# CONNECTIVITY.net
KiCad netlist of a schematic drawn in Altium Designer
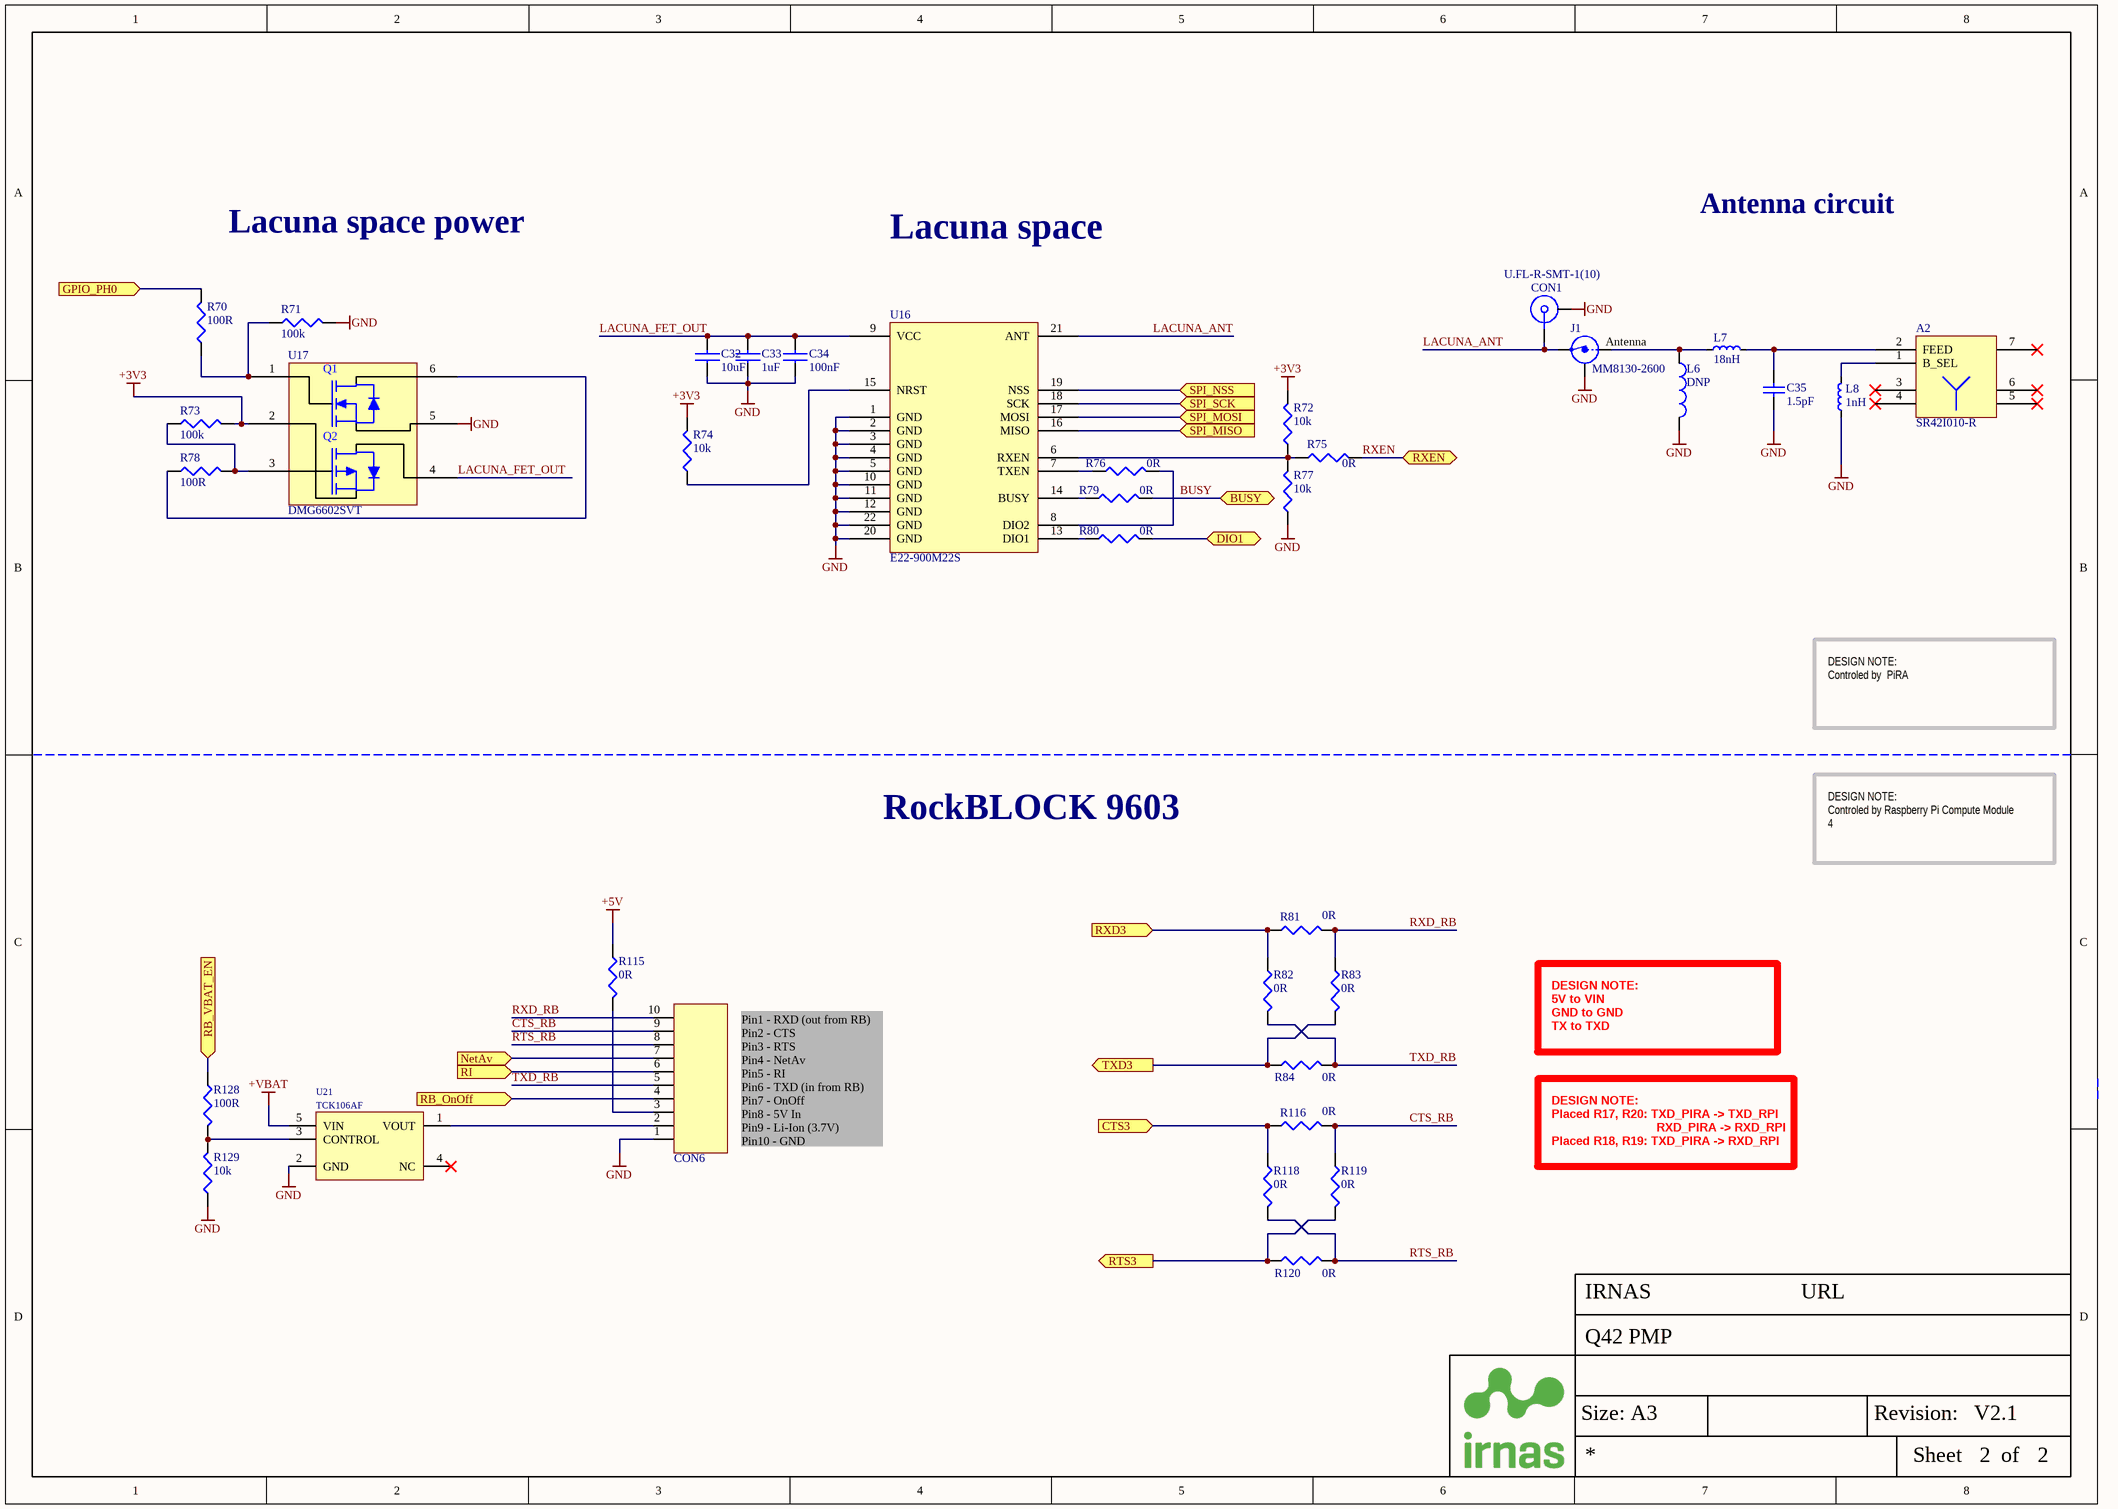
[diagram p0: CONNECTIVITY.SchDoc]

(export (version "E")
  (design (tool "Eeschema 10.0.6"))
  (components
    (comp (ref "A2")
      (value "SR42I010-R")
      (footprint "LORA_PCB_ANTENNA")
      (description "Antenna SMD -4dBi Gain 870MHz/928MHz Automotive 7-Pin SMD T/R")
      (fields (field (name "MANUFACTURER") "Antenova"))
      (libsource (lib "Passive") (part "ANT - SR42I010-L"))
    )
    (comp (ref "C32")
      (value "10uF")
      (footprint "CAP0603")
      (description "Cap Ceramic 10uF 10V X5R 10% SMD 0603 85C Paper T/R")
      (fields
        (field (name "MANUFACTURER") "Samsung")
        (field (name "MANUFACTURER PART NUMBER") "CL10A106KP8NNNC")
      )
      (libsource (lib "Passive") (part "C - 10uF/10V"))
    )
    (comp (ref "C33")
      (value "1uF")
      (footprint "CAP0603")
      (description "MURATA - GRM188R61H105KAALD - CAP, MLCC, X5R, 1UF, 50V, 0603")
      (fields
        (field (name "MANUFACTURER") "MURATA")
        (field (name "MANUFACTURER PART NUMBER") "GRM188R61H105KAALD")
      )
      (libsource (lib "Passive") (part "C - 1uF"))
    )
    (comp (ref "C34")
      (value "100nF")
      (footprint "CAP0603")
      (description "MURATA - GRM188R71C104KA01J - CAP, MLCC, X7R, 0.1UF, 16V, 0603")
      (fields
        (field (name "MANUFACTURER") "MURATA")
        (field (name "MANUFACTURER PART NUMBER") "GRM188R71C104KA01J")
      )
      (libsource (lib "Passive") (part "C - 100nF"))
    )
    (comp (ref "C35")
      (value "1.5pF")
      (footprint "CAP0402")
      (description "CAP CER 1.5PF 50V C0G/NP0 0402")
      (fields (field (name "Comment") "1.5pF/50V/0402") (field (name "PUBLISHER") "Altium Limited"))
      (libsource (lib "Passive") (part "C - 1.5pF/50V/0402"))
    )
    (comp (ref "CON1")
      (value "U.FL-R-SMT-1(10)")
      (footprint "ufl connector smd")
      (description "RF / Coaxial Connector, U.FL Coaxial, Straight Jack, Surface Mount Vertical, 50 ohm, Brass")
      (fields (field (name "MANUFACTURER") "Hirose"))
      (libsource (lib "Connectors") (part "U.FL-R-SMT-1(10)"))
    )
    (comp (ref "CON6")
      (value "53261-1071")
      (footprint "PICOBLADE 10PIN")
      (description "Wire-To-Board Connector, Right Angle, 1.25 mm, 10 Contacts, Header, PicoBlade 53261 Series")
      (libsource (lib "Connectors") (part "PicoBlade 10pin"))
    )
    (comp (ref "J1")
      (value "MM8130-2600")
      (footprint "COAXIAL-SWF")
      (description "Coaxial Connector with Switch")
      (fields
        (field (name "MANUFACTURER") "Murata")
        (field (name "2ND SOURCE PART NUMBER") "81-MM8130-2600RA2")
        (field (name "PUBLISHER") "Nordic Semiconductor")
      )
      (libsource (lib "Connectors") (part "Coaxial-Internal-SW"))
    )
    (comp (ref "L6")
      (value "DNP")
      (footprint "IND0402")
      (description "Inductor RF Chip Multi-Layer 4.3nH 0.3nH 100MHz 8Q-Factor Air 300mA 210mOhm DCR 0402 Paper T/R")
      (fields
        (field (name "MANUFACTURER") "Murata")
        (field (name "MANUFACTURER PART NUMBER") "LQG15HN4N3S02D")
      )
      (libsource (lib "Passive") (part "L - 4.3nH/0402"))
    )
    (comp (ref "L7")
      (value "18nH")
      (footprint "IND0402")
      (description "18 nH, 0.8 ohm, 2.3 GHz, 260 mA, 0402")
      (fields
        (field (name "MANUFACTURER") "MURATA")
        (field (name "MANUFACTURER PART NUMBER") "LQG15WH18NJ02D")
        (field (name "PUBLISHER") "Altium Limited")
      )
      (libsource (lib "Passive") (part "L - 18nH/230mA/0402"))
    )
    (comp (ref "L8")
      (value "1nH")
      (footprint "IND0402")
      (description "Multilayer Inductor, 1 nH, 0.07 ohm, 10 GHz, 1 A, 0402 [1005 Metric], LQG15HS_02 Series")
      (libsource (lib "Passive") (part "L - 1nH/0402"))
    )
    (comp (ref "R70")
      (value "100R")
      (footprint "RES0603")
      (description "MULTICOMP - MC0063W06031100R - RES, THICK FILM, 100R, 1%, 0.063W, 0603")
      (fields
        (field (name "MANUFACTURER") "MULTICOMP")
        (field (name "MANUFACTURER PART NUMBER") "MC0063W06031100R")
      )
      (libsource (lib "Passive") (part "R - 100R"))
    )
    (comp (ref "R71")
      (value "100k")
      (footprint "RES0603")
      (description "MULTICOMP - MCMR06X104 JTL - RES, CERAMIC, 100K, 5%, 0.1W, 0603")
      (fields
        (field (name "MANUFACTURER") "MULTICOMP")
        (field (name "MANUFACTURER PART NUMBER") "MCMR06X104 JTL")
      )
      (libsource (lib "Passive") (part "R - 100k"))
    )
    (comp (ref "R72")
      (value "10k")
      (footprint "RES0603")
      (description "MULTICOMP - MCMR06X103 JTL - RES, CERAMIC, 10K, 5%, 0.1W, 0603")
      (fields
        (field (name "MANUFACTURER") "MULTICOMP")
        (field (name "MANUFACTURER PART NUMBER") "MCMR06X103 JTL")
      )
      (libsource (lib "Passive") (part "R - 10k"))
    )
    (comp (ref "R73")
      (value "100k")
      (footprint "RES0603")
      (description "MULTICOMP - MCMR06X104 JTL - RES, CERAMIC, 100K, 5%, 0.1W, 0603")
      (fields
        (field (name "MANUFACTURER") "MULTICOMP")
        (field (name "MANUFACTURER PART NUMBER") "MCMR06X104 JTL")
      )
      (libsource (lib "Passive") (part "R - 100k"))
    )
    (comp (ref "R74")
      (value "10k")
      (footprint "RES0603")
      (description "MULTICOMP - MCMR06X103 JTL - RES, CERAMIC, 10K, 5%, 0.1W, 0603")
      (fields
        (field (name "MANUFACTURER") "MULTICOMP")
        (field (name "MANUFACTURER PART NUMBER") "MCMR06X103 JTL")
      )
      (libsource (lib "Passive") (part "R - 10k"))
    )
    (comp (ref "R75")
      (value "0R")
      (footprint "RES0603")
      (description "BOURNS - CR0603-J/-000ELF - RES, THICK FILM, 0R, 5%, 0.1W, 0603")
      (fields
        (field (name "MANUFACTURER") "BOURNS")
        (field (name "MANUFACTURER PART NUMBER") "CR0603-J/-000ELF")
      )
      (libsource (lib "Passive") (part "R - 0R"))
    )
    (comp (ref "R76")
      (value "0R")
      (footprint "RES0603")
      (description "BOURNS - CR0603-J/-000ELF - RES, THICK FILM, 0R, 5%, 0.1W, 0603")
      (fields
        (field (name "MANUFACTURER") "BOURNS")
        (field (name "MANUFACTURER PART NUMBER") "CR0603-J/-000ELF")
      )
      (libsource (lib "Passive") (part "R - 0R"))
    )
    (comp (ref "R77")
      (value "10k")
      (footprint "RES0603")
      (description "MULTICOMP - MCMR06X103 JTL - RES, CERAMIC, 10K, 5%, 0.1W, 0603")
      (fields
        (field (name "MANUFACTURER") "MULTICOMP")
        (field (name "MANUFACTURER PART NUMBER") "MCMR06X103 JTL")
      )
      (libsource (lib "Passive") (part "R - 10k"))
    )
    (comp (ref "R78")
      (value "100R")
      (footprint "RES0603")
      (description "MULTICOMP - MC0063W06031100R - RES, THICK FILM, 100R, 1%, 0.063W, 0603")
      (fields
        (field (name "MANUFACTURER") "MULTICOMP")
        (field (name "MANUFACTURER PART NUMBER") "MC0063W06031100R")
      )
      (libsource (lib "Passive") (part "R - 100R"))
    )
    (comp (ref "R79")
      (value "0R")
      (footprint "RES0603")
      (description "BOURNS - CR0603-J/-000ELF - RES, THICK FILM, 0R, 5%, 0.1W, 0603")
      (fields
        (field (name "MANUFACTURER") "BOURNS")
        (field (name "MANUFACTURER PART NUMBER") "CR0603-J/-000ELF")
      )
      (libsource (lib "Passive") (part "R - 0R"))
    )
    (comp (ref "R80")
      (value "0R")
      (footprint "RES0603")
      (description "BOURNS - CR0603-J/-000ELF - RES, THICK FILM, 0R, 5%, 0.1W, 0603")
      (fields
        (field (name "MANUFACTURER") "BOURNS")
        (field (name "MANUFACTURER PART NUMBER") "CR0603-J/-000ELF")
      )
      (libsource (lib "Passive") (part "R - 0R"))
    )
    (comp (ref "R81")
      (value "0R")
      (footprint "RES0603")
      (description "BOURNS - CR0603-J/-000ELF - RES, THICK FILM, 0R, 5%, 0.1W, 0603")
      (fields
        (field (name "MANUFACTURER") "BOURNS")
        (field (name "MANUFACTURER PART NUMBER") "CR0603-J/-000ELF")
      )
      (libsource (lib "Passive") (part "R - 0R"))
    )
    (comp (ref "R82")
      (value "0R")
      (footprint "RES0603")
      (description "BOURNS - CR0603-J/-000ELF - RES, THICK FILM, 0R, 5%, 0.1W, 0603")
      (fields
        (field (name "MANUFACTURER") "BOURNS")
        (field (name "MANUFACTURER PART NUMBER") "CR0603-J/-000ELF")
      )
      (libsource (lib "Passive") (part "R - 0R"))
    )
    (comp (ref "R83")
      (value "0R")
      (footprint "RES0603")
      (description "BOURNS - CR0603-J/-000ELF - RES, THICK FILM, 0R, 5%, 0.1W, 0603")
      (fields
        (field (name "MANUFACTURER") "BOURNS")
        (field (name "MANUFACTURER PART NUMBER") "CR0603-J/-000ELF")
      )
      (libsource (lib "Passive") (part "R - 0R"))
    )
    (comp (ref "R84")
      (value "0R")
      (footprint "RES0603")
      (description "BOURNS - CR0603-J/-000ELF - RES, THICK FILM, 0R, 5%, 0.1W, 0603")
      (fields
        (field (name "MANUFACTURER") "BOURNS")
        (field (name "MANUFACTURER PART NUMBER") "CR0603-J/-000ELF")
      )
      (libsource (lib "Passive") (part "R - 0R"))
    )
    (comp (ref "R115")
      (value "0R")
      (footprint "RES0603")
      (description "BOURNS - CR0603-J/-000ELF - RES, THICK FILM, 0R, 5%, 0.1W, 0603")
      (fields
        (field (name "MANUFACTURER") "BOURNS")
        (field (name "MANUFACTURER PART NUMBER") "CR0603-J/-000ELF")
      )
      (libsource (lib "Passive") (part "R - 0R"))
    )
    (comp (ref "R116")
      (value "0R")
      (footprint "RES0603")
      (description "BOURNS - CR0603-J/-000ELF - RES, THICK FILM, 0R, 5%, 0.1W, 0603")
      (fields
        (field (name "MANUFACTURER") "BOURNS")
        (field (name "MANUFACTURER PART NUMBER") "CR0603-J/-000ELF")
      )
      (libsource (lib "Passive") (part "R - 0R"))
    )
    (comp (ref "R118")
      (value "0R")
      (footprint "RES0603")
      (description "BOURNS - CR0603-J/-000ELF - RES, THICK FILM, 0R, 5%, 0.1W, 0603")
      (fields
        (field (name "MANUFACTURER") "BOURNS")
        (field (name "MANUFACTURER PART NUMBER") "CR0603-J/-000ELF")
      )
      (libsource (lib "Passive") (part "R - 0R"))
    )
    (comp (ref "R119")
      (value "0R")
      (footprint "RES0603")
      (description "BOURNS - CR0603-J/-000ELF - RES, THICK FILM, 0R, 5%, 0.1W, 0603")
      (fields
        (field (name "MANUFACTURER") "BOURNS")
        (field (name "MANUFACTURER PART NUMBER") "CR0603-J/-000ELF")
      )
      (libsource (lib "Passive") (part "R - 0R"))
    )
    (comp (ref "R120")
      (value "0R")
      (footprint "RES0603")
      (description "BOURNS - CR0603-J/-000ELF - RES, THICK FILM, 0R, 5%, 0.1W, 0603")
      (fields
        (field (name "MANUFACTURER") "BOURNS")
        (field (name "MANUFACTURER PART NUMBER") "CR0603-J/-000ELF")
      )
      (libsource (lib "Passive") (part "R - 0R"))
    )
    (comp (ref "R128")
      (value "100R")
      (footprint "RES0603")
      (description "MULTICOMP - MC0063W06031100R - RES, THICK FILM, 100R, 1%, 0.063W, 0603")
      (fields
        (field (name "MANUFACTURER") "MULTICOMP")
        (field (name "MANUFACTURER PART NUMBER") "MC0063W06031100R")
      )
      (libsource (lib "Passive") (part "R - 100R"))
    )
    (comp (ref "R129")
      (value "10k")
      (footprint "RES0603")
      (description "MULTICOMP - MCMR06X103 JTL - RES, CERAMIC, 10K, 5%, 0.1W, 0603")
      (fields
        (field (name "MANUFACTURER") "MULTICOMP")
        (field (name "MANUFACTURER PART NUMBER") "MCMR06X103 JTL")
      )
      (libsource (lib "Passive") (part "R - 10k"))
    )
    (comp (ref "U16")
      (value "E22-900M22S")
      (footprint "E22-900M22S")
      (libsource (lib "Active") (part "RF - E22-900M22S"))
    )
    (comp (ref "U17")
      (value "DMG6602SVT")
      (footprint "TSOT26")
      (description "Dual MOSFET, N and P Channel, 3.4 A, 30 V, 0.038 ohm, 10 V, 1 V")
      (libsource (lib "Active") (part "T_M - DMG6602SVT"))
    )
    (comp (ref "U21")
      (value "TCK106AF")
      (footprint "SOT-25")
      (description "1.0 A Load Switch IC")
      (libsource (lib "Active") (part "SW - TCK106AF"))
    )
  )
  (nets
    (net (code "1") (name "+3V3") (class "Default")
      (node (ref "R72") (pin "2") (pinfunction "2_2") (pintype "passive"))
      (node (ref "R73") (pin "2") (pinfunction "2_2") (pintype "passive"))
      (node (ref "R74") (pin "2") (pinfunction "2_2") (pintype "passive"))
      (node (ref "U17") (pin "2") (pinfunction "S2_2") (pintype "open_collector"))
    )
    (net (code "2") (name "+5V") (class "Default")
      (node (ref "R115") (pin "1") (pinfunction "1_1") (pintype "passive"))
    )
    (net (code "3") (name "+VBAT") (class "Default")
      (node (ref "U21") (pin "5") (pinfunction "VIN_5") (pintype "passive"))
    )
    (net (code "4") (name "/BUSY") (class "Default")
      (node (ref "R79") (pin "2") (pinfunction "2_2") (pintype "passive"))
    )
    (net (code "5") (name "/CTS3") (class "Default")
      (node (ref "R116") (pin "1") (pinfunction "1_1") (pintype "passive"))
      (node (ref "R118") (pin "1") (pinfunction "1_1") (pintype "passive"))
    )
    (net (code "6") (name "/CTS_RB") (class "Default")
      (node (ref "CON6") (pin "9") (pinfunction "9_9") (pintype "passive"))
      (node (ref "R116") (pin "2") (pinfunction "2_2") (pintype "passive"))
      (node (ref "R119") (pin "1") (pinfunction "1_1") (pintype "passive"))
    )
    (net (code "7") (name "/DIO1") (class "Default")
      (node (ref "R80") (pin "2") (pinfunction "2_2") (pintype "passive"))
    )
    (net (code "8") (name "/GPIO_PH0") (class "Default")
      (node (ref "R70") (pin "2") (pinfunction "2_2") (pintype "passive"))
    )
    (net (code "9") (name "/LACUNA_ANT") (class "Default")
      (node (ref "CON1") (pin "1") (pinfunction "1_1") (pintype "open_collector"))
      (node (ref "J1") (pin "3") (pinfunction "OUT_3") (pintype "passive"))
      (node (ref "U16") (pin "21") (pinfunction "ANT_21") (pintype "passive"))
    )
    (net (code "10") (name "/LACUNA_FET_OUT") (class "Default")
      (node (ref "C32") (pin "2") (pinfunction "2_2") (pintype "passive"))
      (node (ref "C33") (pin "2") (pinfunction "2_2") (pintype "passive"))
      (node (ref "C34") (pin "2") (pinfunction "2_2") (pintype "passive"))
      (node (ref "U16") (pin "9") (pinfunction "VCC_9") (pintype "passive"))
      (node (ref "U17") (pin "4") (pinfunction "D2_4") (pintype "open_collector"))
    )
    (net (code "11") (name "/NetAv") (class "Default")
      (node (ref "CON6") (pin "7") (pinfunction "7_7") (pintype "passive"))
    )
    (net (code "12") (name "/RB_OnOff") (class "Default")
      (node (ref "CON6") (pin "4") (pinfunction "4_4") (pintype "passive"))
    )
    (net (code "13") (name "/RB_VBAT_EN") (class "Default")
      (node (ref "R128") (pin "1") (pinfunction "1_1") (pintype "passive"))
    )
    (net (code "14") (name "/RI") (class "Default")
      (node (ref "CON6") (pin "6") (pinfunction "6_6") (pintype "passive"))
    )
    (net (code "15") (name "/RTS3") (class "Default")
      (node (ref "R119") (pin "2") (pinfunction "2_2") (pintype "passive"))
      (node (ref "R120") (pin "1") (pinfunction "1_1") (pintype "passive"))
    )
    (net (code "16") (name "/RTS_RB") (class "Default")
      (node (ref "CON6") (pin "8") (pinfunction "8_8") (pintype "passive"))
      (node (ref "R118") (pin "2") (pinfunction "2_2") (pintype "passive"))
      (node (ref "R120") (pin "2") (pinfunction "2_2") (pintype "passive"))
    )
    (net (code "17") (name "/RXD3") (class "Default")
      (node (ref "R81") (pin "1") (pinfunction "1_1") (pintype "passive"))
      (node (ref "R82") (pin "1") (pinfunction "1_1") (pintype "passive"))
    )
    (net (code "18") (name "/RXD_RB") (class "Default")
      (node (ref "CON6") (pin "10") (pinfunction "10_10") (pintype "passive"))
      (node (ref "R81") (pin "2") (pinfunction "2_2") (pintype "passive"))
      (node (ref "R83") (pin "1") (pinfunction "1_1") (pintype "passive"))
    )
    (net (code "19") (name "/RXEN") (class "Default")
      (node (ref "R75") (pin "2") (pinfunction "2_2") (pintype "passive"))
    )
    (net (code "20") (name "/SPI_MISO") (class "Default")
      (node (ref "U16") (pin "16") (pinfunction "MISO_16") (pintype "passive"))
    )
    (net (code "21") (name "/SPI_MOSI") (class "Default")
      (node (ref "U16") (pin "17") (pinfunction "MOSI_17") (pintype "passive"))
    )
    (net (code "22") (name "/SPI_NSS") (class "Default")
      (node (ref "U16") (pin "19") (pinfunction "NSS_19") (pintype "passive"))
    )
    (net (code "23") (name "/SPI_SCK") (class "Default")
      (node (ref "U16") (pin "18") (pinfunction "SCK_18") (pintype "passive"))
    )
    (net (code "24") (name "/TXD3") (class "Default")
      (node (ref "R83") (pin "2") (pinfunction "2_2") (pintype "passive"))
      (node (ref "R84") (pin "1") (pinfunction "1_1") (pintype "passive"))
    )
    (net (code "25") (name "/TXD_RB") (class "Default")
      (node (ref "CON6") (pin "5") (pinfunction "5_5") (pintype "passive"))
      (node (ref "R82") (pin "2") (pinfunction "2_2") (pintype "passive"))
      (node (ref "R84") (pin "2") (pinfunction "2_2") (pintype "passive"))
    )
    (net (code "26") (name "GND") (class "Default")
      (node (ref "C32") (pin "1") (pinfunction "1_1") (pintype "passive"))
      (node (ref "C33") (pin "1") (pinfunction "1_1") (pintype "passive"))
      (node (ref "C34") (pin "1") (pinfunction "1_1") (pintype "passive"))
      (node (ref "C35") (pin "1") (pinfunction "1_1") (pintype "passive"))
      (node (ref "CON1") (pin "2") (pinfunction "2_2") (pintype "passive"))
      (node (ref "CON6") (pin "1") (pinfunction "1_1") (pintype "passive"))
      (node (ref "J1") (pin "2") (pinfunction "Shield_2") (pintype "passive"))
      (node (ref "L6") (pin "1") (pinfunction "1_1") (pintype "passive"))
      (node (ref "L8") (pin "1") (pinfunction "1_1") (pintype "passive"))
      (node (ref "R129") (pin "1") (pinfunction "1_1") (pintype "passive"))
      (node (ref "R71") (pin "2") (pinfunction "2_2") (pintype "passive"))
      (node (ref "R77") (pin "1") (pinfunction "1_1") (pintype "passive"))
      (node (ref "U16") (pin "1") (pinfunction "GND_1") (pintype "passive"))
      (node (ref "U16") (pin "10") (pinfunction "GND_10") (pintype "passive"))
      (node (ref "U16") (pin "11") (pinfunction "GND_11") (pintype "passive"))
      (node (ref "U16") (pin "12") (pinfunction "GND_12") (pintype "passive"))
      (node (ref "U16") (pin "2") (pinfunction "GND_2") (pintype "passive"))
      (node (ref "U16") (pin "20") (pinfunction "GND_20") (pintype "passive"))
      (node (ref "U16") (pin "22") (pinfunction "GND_22") (pintype "passive"))
      (node (ref "U16") (pin "3") (pinfunction "GND_3") (pintype "passive"))
      (node (ref "U16") (pin "4") (pinfunction "GND_4") (pintype "passive"))
      (node (ref "U16") (pin "5") (pinfunction "GND_5") (pintype "passive"))
      (node (ref "U17") (pin "5") (pinfunction "S1_5") (pintype "passive"))
      (node (ref "U21") (pin "2") (pinfunction "GND_2") (pintype "passive"))
    )
    (net (code "27") (name "Net-(A2-B_SEL)") (class "Default")
      (node (ref "A2") (pin "1") (pinfunction "B_SEL_1") (pintype "passive"))
      (node (ref "L8") (pin "2") (pinfunction "2_2") (pintype "passive"))
    )
    (net (code "28") (name "Net-(A2-FEED)") (class "Default")
      (node (ref "A2") (pin "2") (pinfunction "FEED_2") (pintype "passive"))
      (node (ref "C35") (pin "2") (pinfunction "2_2") (pintype "passive"))
      (node (ref "L7") (pin "2") (pinfunction "2_2") (pintype "passive"))
    )
    (net (code "29") (name "Net-(CON6-Pad3)") (class "Default")
      (node (ref "CON6") (pin "3") (pinfunction "3_3") (pintype "passive"))
      (node (ref "R115") (pin "2") (pinfunction "2_2") (pintype "passive"))
    )
    (net (code "30") (name "Net-(J1-IN)") (class "Default")
      (node (ref "J1") (pin "1") (pinfunction "IN_1") (pintype "passive"))
      (node (ref "L6") (pin "2") (pinfunction "2_2") (pintype "passive"))
      (node (ref "L7") (pin "1") (pinfunction "1_1") (pintype "passive"))
    )
    (net (code "31") (name "Net-(U16-BUSY)") (class "Default")
      (node (ref "R79") (pin "1") (pinfunction "1_1") (pintype "passive"))
      (node (ref "U16") (pin "14") (pinfunction "BUSY_14") (pintype "passive"))
    )
    (net (code "32") (name "Net-(U16-DIO1)") (class "Default")
      (node (ref "R80") (pin "1") (pinfunction "1_1") (pintype "passive"))
      (node (ref "U16") (pin "13") (pinfunction "DIO1_13") (pintype "passive"))
    )
    (net (code "33") (name "Net-(U16-DIO2)") (class "Default")
      (node (ref "R76") (pin "2") (pinfunction "2_2") (pintype "passive"))
      (node (ref "U16") (pin "8") (pinfunction "DIO2_8") (pintype "passive"))
    )
    (net (code "34") (name "Net-(U16-NRST)") (class "Default")
      (node (ref "R74") (pin "1") (pinfunction "1_1") (pintype "passive"))
      (node (ref "U16") (pin "15") (pinfunction "NRST_15") (pintype "passive"))
    )
    (net (code "35") (name "Net-(U16-RXEN)") (class "Default")
      (node (ref "R72") (pin "1") (pinfunction "1_1") (pintype "passive"))
      (node (ref "R75") (pin "1") (pinfunction "1_1") (pintype "passive"))
      (node (ref "R77") (pin "2") (pinfunction "2_2") (pintype "passive"))
      (node (ref "U16") (pin "6") (pinfunction "RXEN_6") (pintype "passive"))
    )
    (net (code "36") (name "Net-(U16-TXEN)") (class "Default")
      (node (ref "R76") (pin "1") (pinfunction "1_1") (pintype "passive"))
      (node (ref "U16") (pin "7") (pinfunction "TXEN_7") (pintype "passive"))
    )
    (net (code "37") (name "Net-(U17-D1)") (class "Default")
      (node (ref "R78") (pin "1") (pinfunction "1_1") (pintype "passive"))
      (node (ref "U17") (pin "6") (pinfunction "D1_6") (pintype "open_collector"))
    )
    (net (code "38") (name "Net-(U17-G1)") (class "Default")
      (node (ref "R70") (pin "1") (pinfunction "1_1") (pintype "passive"))
      (node (ref "R71") (pin "1") (pinfunction "1_1") (pintype "passive"))
      (node (ref "U17") (pin "1") (pinfunction "G1_1") (pintype "open_collector"))
    )
    (net (code "39") (name "Net-(U17-G2)") (class "Default")
      (node (ref "R73") (pin "1") (pinfunction "1_1") (pintype "passive"))
      (node (ref "R78") (pin "2") (pinfunction "2_2") (pintype "passive"))
      (node (ref "U17") (pin "3") (pinfunction "G2_3") (pintype "open_collector"))
    )
    (net (code "40") (name "Net-(U21-CONTROL)") (class "Default")
      (node (ref "R128") (pin "2") (pinfunction "2_2") (pintype "passive"))
      (node (ref "R129") (pin "2") (pinfunction "2_2") (pintype "passive"))
      (node (ref "U21") (pin "3") (pinfunction "CONTROL_3") (pintype "passive"))
    )
    (net (code "41") (name "Net-(U21-VOUT)") (class "Default")
      (node (ref "CON6") (pin "2") (pinfunction "2_2") (pintype "passive"))
      (node (ref "U21") (pin "1") (pinfunction "VOUT_1") (pintype "passive"))
    )
    (net (code "42") (name "unconnected-(A2-Pad3)") (class "Default")
      (node (ref "A2") (pin "3") (pintype "passive+no_connect"))
    )
    (net (code "43") (name "unconnected-(A2-Pad4)") (class "Default")
      (node (ref "A2") (pin "4") (pintype "passive+no_connect"))
    )
    (net (code "44") (name "unconnected-(A2-Pad5)") (class "Default")
      (node (ref "A2") (pin "5") (pintype "passive+no_connect"))
    )
    (net (code "45") (name "unconnected-(A2-Pad6)") (class "Default")
      (node (ref "A2") (pin "6") (pintype "passive+no_connect"))
    )
    (net (code "46") (name "unconnected-(A2-Pad7)") (class "Default")
      (node (ref "A2") (pin "7") (pintype "passive+no_connect"))
    )
    (net (code "47") (name "unconnected-(U21-NC-Pad4)") (class "Default")
      (node (ref "U21") (pin "4") (pinfunction "NC_4") (pintype "passive+no_connect"))
    )
  )
)
